# Voltage_Regulator.net
KiCad netlist of a schematic drawn in EAGLE
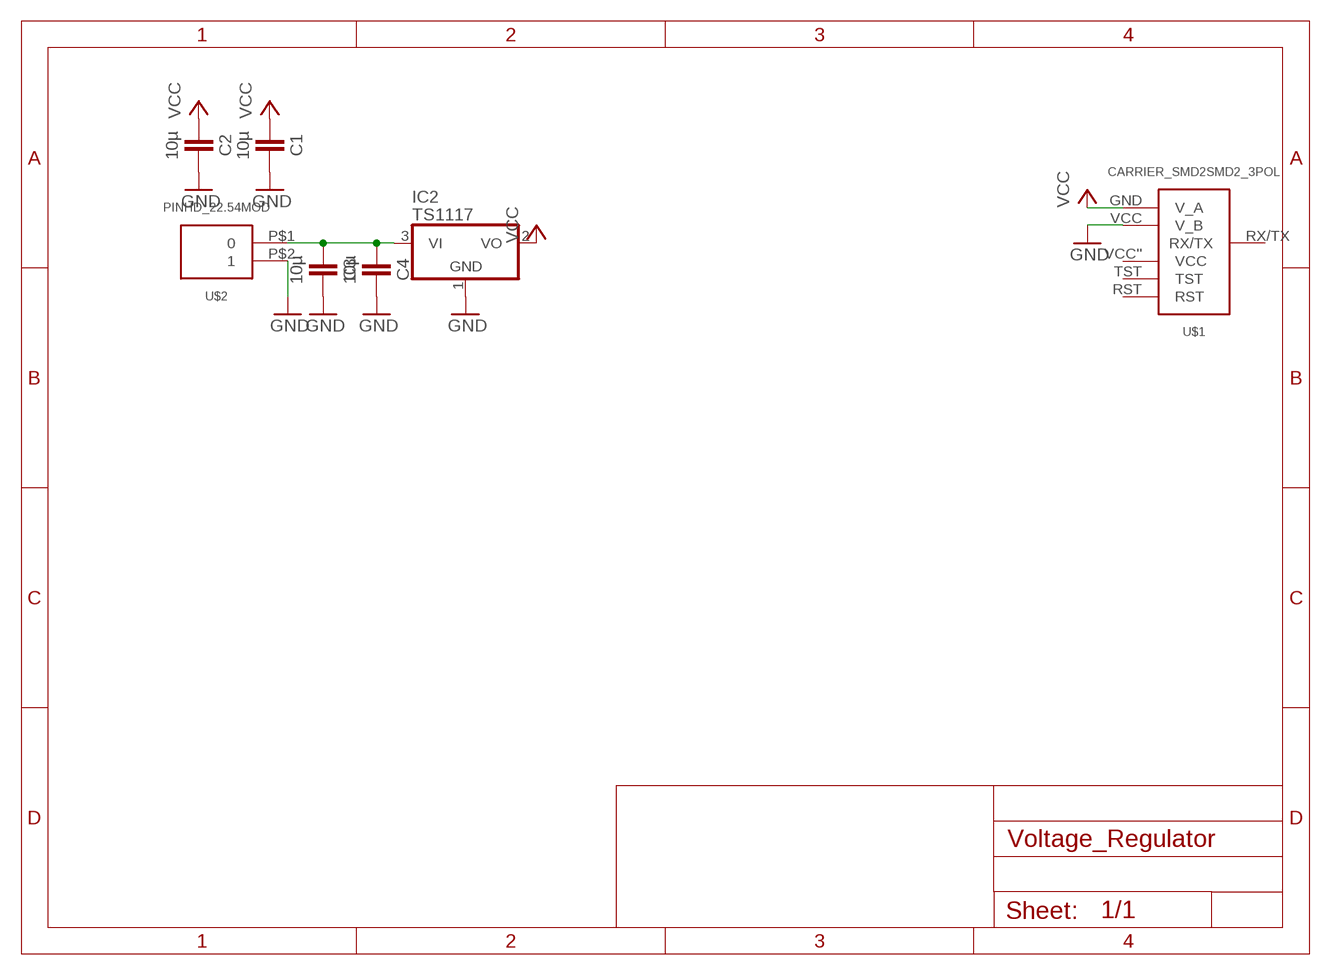
[diagram p0: schematic, sheet 1]

(export (version "E")
  (design (tool "Eeschema 10.0.6"))
  (components
    (comp (ref "C1")
      (value "10µ")
      (footprint "eagle-import:1206")
      (libsource (lib "eagle-import") (part "CAPACITOR1206"))
    )
    (comp (ref "C2")
      (value "10µ")
      (footprint "eagle-import:1206")
      (libsource (lib "eagle-import") (part "CAPACITOR1206"))
    )
    (comp (ref "C3")
      (value "10µ")
      (footprint "eagle-import:1206")
      (libsource (lib "eagle-import") (part "CAPACITOR1206"))
    )
    (comp (ref "C4")
      (value "10µ")
      (footprint "eagle-import:1206")
      (libsource (lib "eagle-import") (part "CAPACITOR1206"))
    )
    (comp (ref "IC2")
      (value "TS1117")
      (footprint "eagle-import:SOT223")
      (libsource (lib "eagle-import") (part "TS1117"))
    )
    (comp (ref "U$1")
      (value "CARRIER_SMD2SMD2_3POL")
      (footprint "eagle-import:CARRIER_SMD2_3POL")
      (libsource (lib "eagle-import") (part "CARRIER_SMD2SMD2_3POL"))
    )
    (comp (ref "U$2")
      (value "PINHD_22.54MOD")
      (footprint "eagle-import:PINHD_2_MOD")
      (libsource (lib "eagle-import") (part "PINHD_22.54MOD"))
    )
  )
  (nets
    (net (code "1") (name "GND") (class "Default")
      (node (ref "C1") (pin "2") (pinfunction "2_2") (pintype "passive"))
      (node (ref "C2") (pin "2") (pinfunction "2_2") (pintype "passive"))
      (node (ref "C3") (pin "2") (pinfunction "2_2") (pintype "passive"))
      (node (ref "C4") (pin "2") (pinfunction "2_2") (pintype "passive"))
      (node (ref "IC2") (pin "1") (pinfunction "GND_1") (pintype "passive"))
      (node (ref "U$1") (pin "VCC") (pinfunction "V_B_VCC") (pintype "bidirectional"))
      (node (ref "U$2") (pin "P$2") (pinfunction "1_P$2") (pintype "bidirectional"))
    )
    (net (code "2") (name "Net-(IC2-VI)") (class "Default")
      (node (ref "C3") (pin "1") (pinfunction "1_1") (pintype "passive"))
      (node (ref "C4") (pin "1") (pinfunction "1_1") (pintype "passive"))
      (node (ref "IC2") (pin "3") (pinfunction "VI_3") (pintype "input"))
      (node (ref "U$2") (pin "P$1") (pinfunction "0_P$1") (pintype "bidirectional"))
    )
    (net (code "3") (name "VCC") (class "Default")
      (node (ref "C1") (pin "1") (pinfunction "1_1") (pintype "passive"))
      (node (ref "C2") (pin "1") (pinfunction "1_1") (pintype "passive"))
      (node (ref "IC2") (pin "2") (pinfunction "VO_2") (pintype "passive"))
      (node (ref "U$1") (pin "GND") (pinfunction "V_A_GND") (pintype "bidirectional"))
    )
    (net (code "4") (name "unconnected-(U$1-PadRST)") (class "Default")
      (node (ref "U$1") (pin "RST") (pinfunction "RST_RST") (pintype "bidirectional"))
    )
    (net (code "5") (name "unconnected-(U$1-PadRX{slash}TX)") (class "Default")
      (node (ref "U$1") (pin "RX/TX") (pinfunction "RX/TX_RX/TX") (pintype "bidirectional"))
    )
    (net (code "6") (name "unconnected-(U$1-PadTST)") (class "Default")
      (node (ref "U$1") (pin "TST") (pinfunction "TST_TST") (pintype "bidirectional"))
    )
    (net (code "7") (name "unconnected-(U$1-VCC-PadVCC'')") (class "Default")
      (node (ref "U$1") (pin "VCC''") (pinfunction "VCC_VCC''") (pintype "bidirectional"))
    )
  )
)
